# DRV8210PDSGR_2ways.net
KiCad netlist of a schematic drawn in EasyEDA Pro
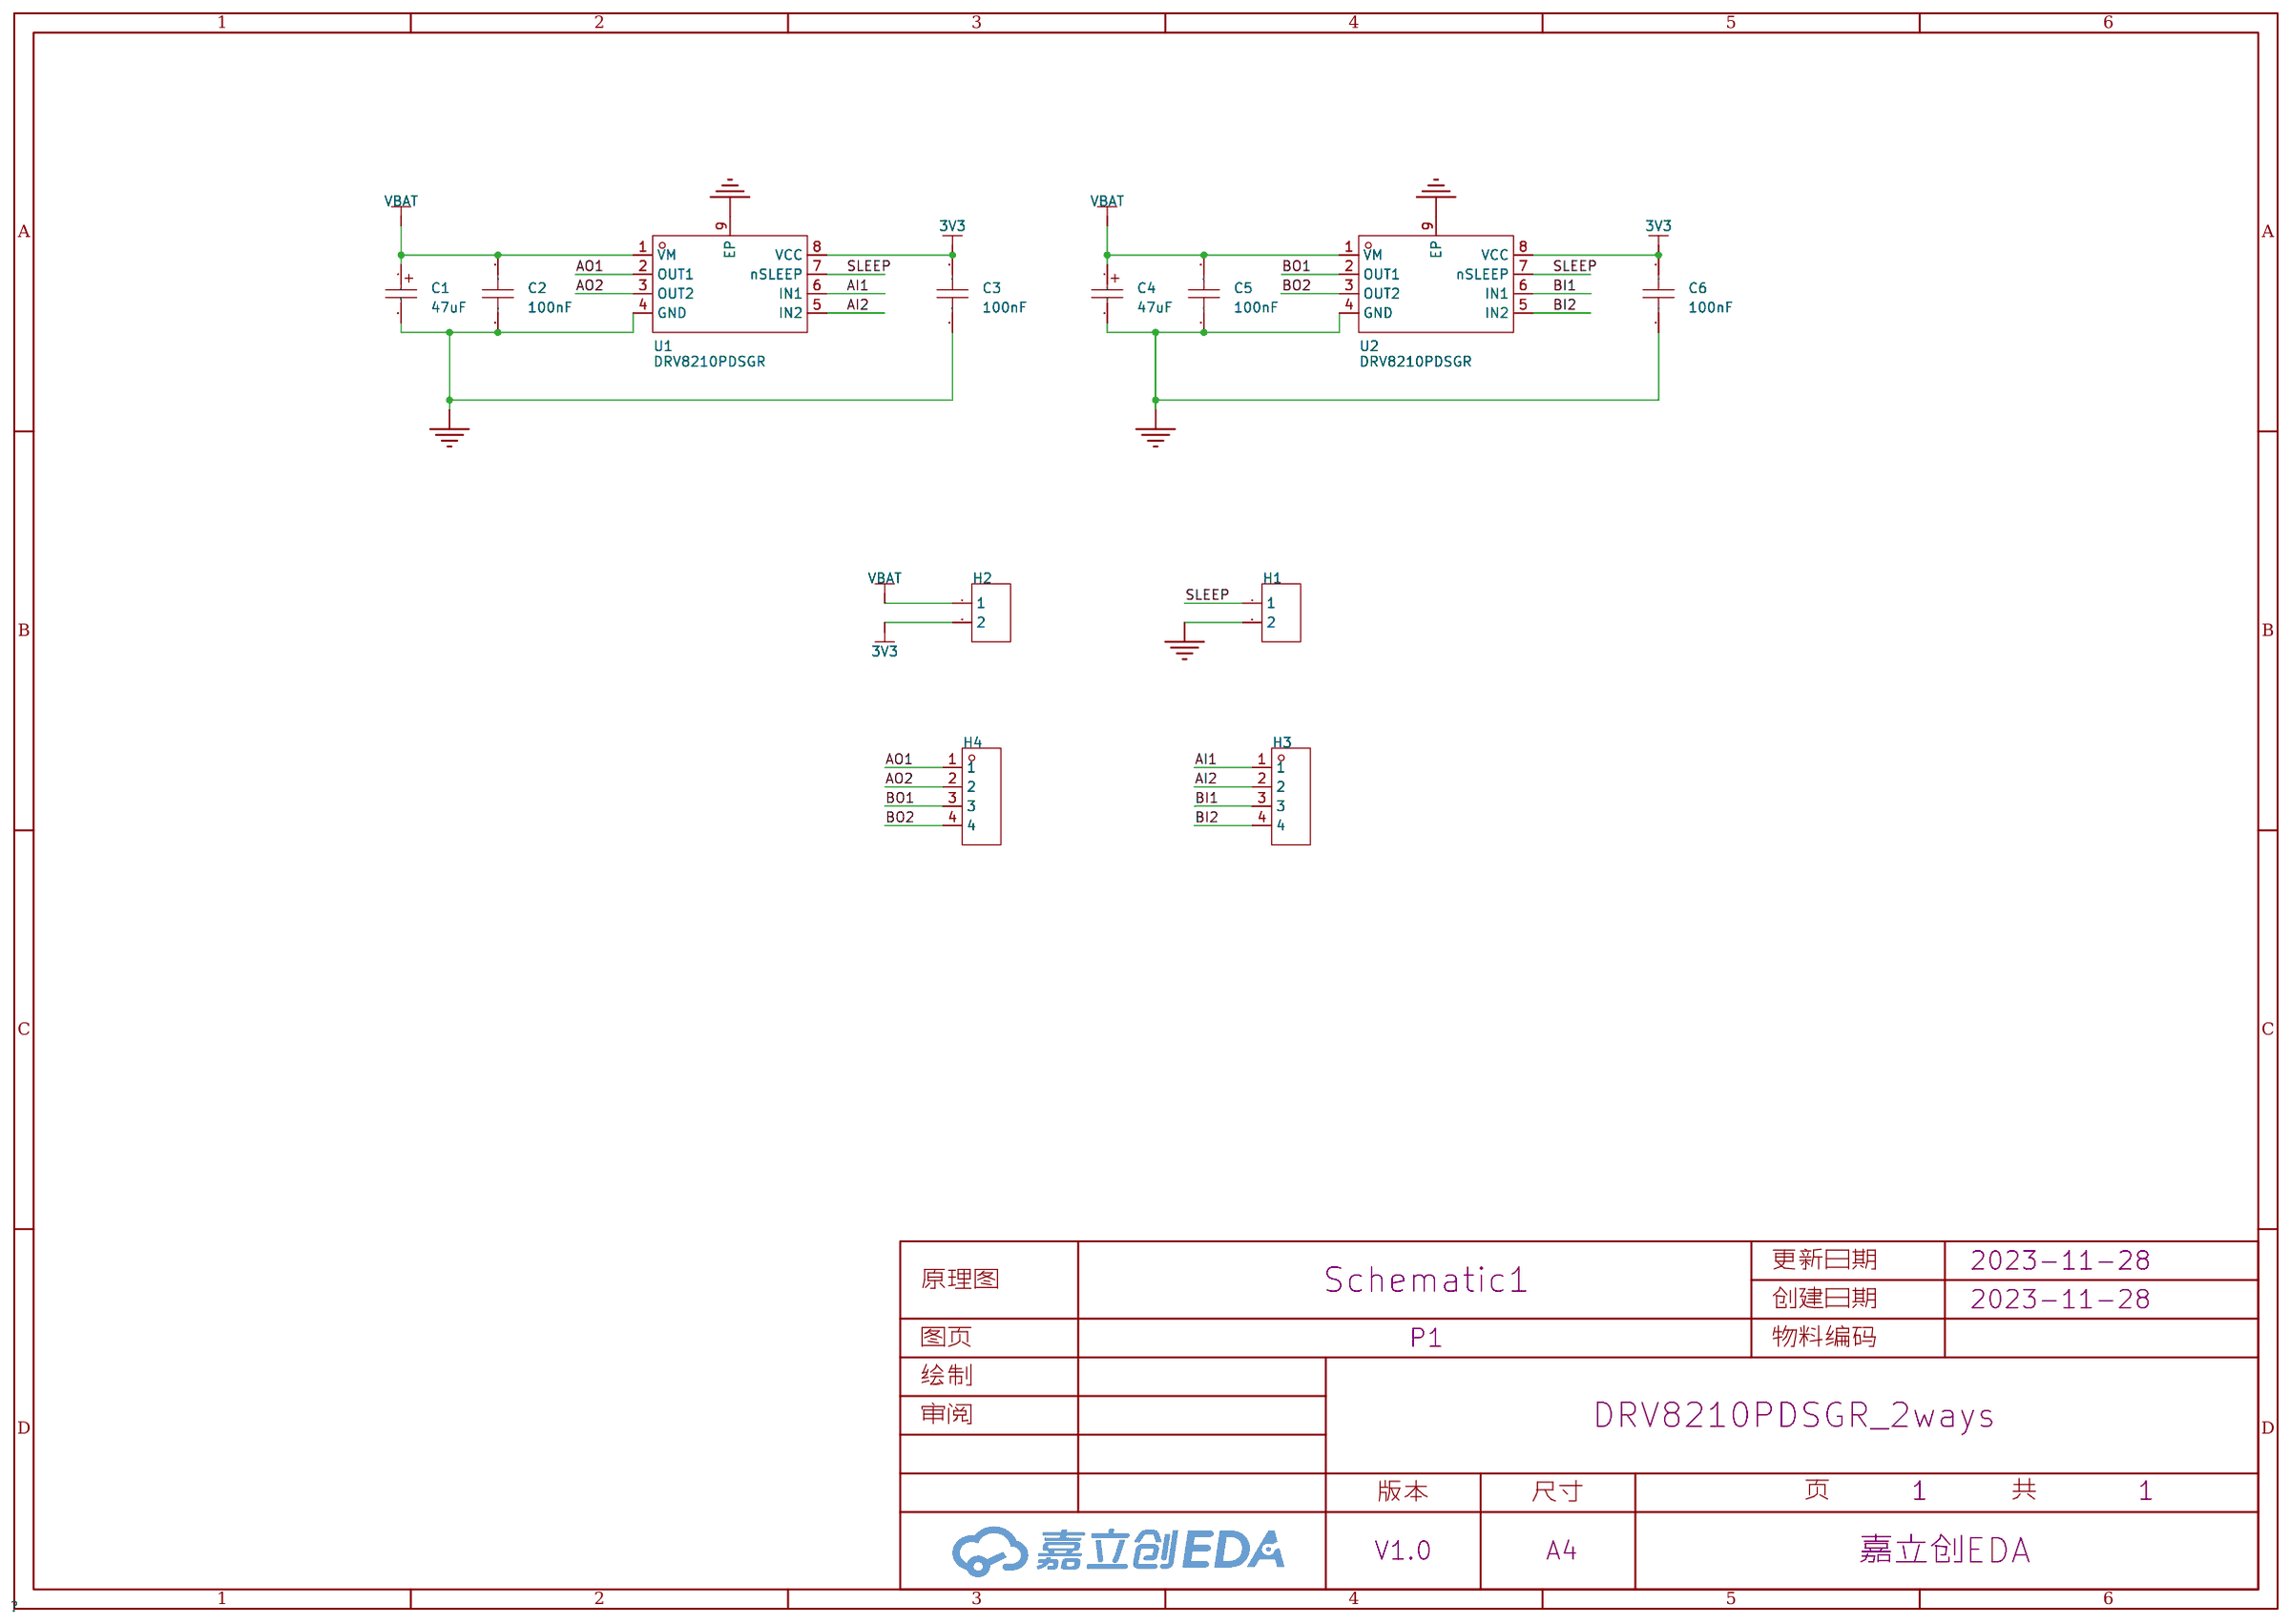
[diagram p0: schematic sheet]

(export (version "E")
  (design (tool "Eeschema 10.0.6"))
  (components
    (comp (ref "C1")
      (value "47uF")
      (footprint "easyedapro:CAP-SMD_L3.5-W2.8-R-RD")
      (description "容值:47uF;精度:±10%;额定电压:10V;等效串联电阻:1Ω@100kHz;")
      (fields (field (name "Manufacturer Part") "CA45-B010K476T") (field (name "Manufacturer") "湘怡中元/湘江"))
      (libsource (lib "easyedapro") (part "CA45-B010K476T"))
    )
    (comp (ref "C2")
      (value "100nF")
      (footprint "easyedapro:C0402")
      (libsource (lib "easyedapro") (part "CapAcitance"))
    )
    (comp (ref "C3")
      (value "100nF")
      (footprint "easyedapro:C0402")
      (libsource (lib "easyedapro") (part "CapAcitance"))
    )
    (comp (ref "C4")
      (value "47uF")
      (footprint "easyedapro:CAP-SMD_L3.5-W2.8-R-RD")
      (description "容值:47uF;精度:±10%;额定电压:10V;等效串联电阻:1Ω@100kHz;")
      (fields (field (name "Manufacturer Part") "CA45-B010K476T") (field (name "Manufacturer") "湘怡中元/湘江"))
      (libsource (lib "easyedapro") (part "CA45-B010K476T"))
    )
    (comp (ref "C5")
      (value "100nF")
      (footprint "easyedapro:C0402")
      (libsource (lib "easyedapro") (part "CapAcitance"))
    )
    (comp (ref "C6")
      (value "100nF")
      (footprint "easyedapro:C0402")
      (libsource (lib "easyedapro") (part "CapAcitance"))
    )
    (comp (ref "H1")
      (value "~")
      (footprint "easyedapro:HDR-TH_2P-P2.54-V-F")
      (libsource (lib "easyedapro") (part "Header-Female-2.54_1x2"))
    )
    (comp (ref "H2")
      (value "~")
      (footprint "easyedapro:HDR-TH_2P-P2.54-V-F")
      (libsource (lib "easyedapro") (part "Header-Female-2.54_1x2"))
    )
    (comp (ref "H3")
      (value "~")
      (footprint "easyedapro:HDR-TH_4P-P2.54-V-F")
      (libsource (lib "easyedapro") (part "2.54-1*4P母"))
    )
    (comp (ref "H4")
      (value "~")
      (footprint "easyedapro:HDR-TH_4P-P2.54-V-F")
      (libsource (lib "easyedapro") (part "2.54-1*4P母"))
    )
    (comp (ref "U1")
      (value "DRV8210PDSGR")
      (footprint "easyedapro:WSON-8_L2.0-W2.0-P0.50-TL-EP")
      (description "类型:有刷直流电机;电源电压:1.65V~12V;输出电流:1.76A;接口:PWM;")
      (fields (field (name "Manufacturer") "TI(德州仪器)"))
      (libsource (lib "easyedapro") (part "DRV8210PDSGR"))
    )
    (comp (ref "U2")
      (value "DRV8210PDSGR")
      (footprint "easyedapro:WSON-8_L2.0-W2.0-P0.50-TL-EP")
      (description "类型:有刷直流电机;电源电压:1.65V~12V;输出电流:1.76A;接口:PWM;")
      (fields (field (name "Manufacturer") "TI(德州仪器)"))
      (libsource (lib "easyedapro") (part "DRV8210PDSGR"))
    )
  )
  (nets
    (net (code "1") (name "/AI1") (class "Default")
      (node (ref "H3") (pin "1") (pinfunction "1_1") (pintype "unspecified"))
      (node (ref "U1") (pin "6") (pinfunction "IN1_6") (pintype "unspecified"))
    )
    (net (code "2") (name "/AI2") (class "Default")
      (node (ref "H3") (pin "2") (pinfunction "2_2") (pintype "unspecified"))
      (node (ref "U1") (pin "5") (pinfunction "IN2_5") (pintype "unspecified"))
    )
    (net (code "3") (name "/AO1") (class "Default")
      (node (ref "H4") (pin "1") (pinfunction "1_1") (pintype "unspecified"))
      (node (ref "U1") (pin "2") (pinfunction "OUT1_2") (pintype "unspecified"))
    )
    (net (code "4") (name "/AO2") (class "Default")
      (node (ref "H4") (pin "2") (pinfunction "2_2") (pintype "unspecified"))
      (node (ref "U1") (pin "3") (pinfunction "OUT2_3") (pintype "unspecified"))
    )
    (net (code "5") (name "/BI1") (class "Default")
      (node (ref "H3") (pin "3") (pinfunction "3_3") (pintype "unspecified"))
      (node (ref "U2") (pin "6") (pinfunction "IN1_6") (pintype "unspecified"))
    )
    (net (code "6") (name "/BI2") (class "Default")
      (node (ref "H3") (pin "4") (pinfunction "4_4") (pintype "unspecified"))
      (node (ref "U2") (pin "5") (pinfunction "IN2_5") (pintype "unspecified"))
    )
    (net (code "7") (name "/BO1") (class "Default")
      (node (ref "H4") (pin "3") (pinfunction "3_3") (pintype "unspecified"))
      (node (ref "U2") (pin "2") (pinfunction "OUT1_2") (pintype "unspecified"))
    )
    (net (code "8") (name "/BO2") (class "Default")
      (node (ref "H4") (pin "4") (pinfunction "4_4") (pintype "unspecified"))
      (node (ref "U2") (pin "3") (pinfunction "OUT2_3") (pintype "unspecified"))
    )
    (net (code "9") (name "/SLEEP") (class "Default")
      (node (ref "H1") (pin "1") (pinfunction "1_1") (pintype "input"))
      (node (ref "U1") (pin "7") (pinfunction "nSLEEP_7") (pintype "unspecified"))
      (node (ref "U2") (pin "7") (pinfunction "nSLEEP_7") (pintype "unspecified"))
    )
    (net (code "10") (name "3V3") (class "Default")
      (node (ref "C3") (pin "2") (pinfunction "2_2") (pintype "input"))
      (node (ref "C6") (pin "2") (pinfunction "2_2") (pintype "input"))
      (node (ref "H2") (pin "2") (pinfunction "2_2") (pintype "input"))
      (node (ref "U1") (pin "8") (pinfunction "VCC_8") (pintype "unspecified"))
      (node (ref "U2") (pin "8") (pinfunction "VCC_8") (pintype "unspecified"))
    )
    (net (code "11") (name "GND") (class "Default")
      (node (ref "C1") (pin "2") (pinfunction "2_2") (pintype "input"))
      (node (ref "C2") (pin "1") (pinfunction "1_1") (pintype "input"))
      (node (ref "C3") (pin "1") (pinfunction "1_1") (pintype "input"))
      (node (ref "C4") (pin "2") (pinfunction "2_2") (pintype "input"))
      (node (ref "C5") (pin "1") (pinfunction "1_1") (pintype "input"))
      (node (ref "C6") (pin "1") (pinfunction "1_1") (pintype "input"))
      (node (ref "H1") (pin "2") (pinfunction "2_2") (pintype "input"))
      (node (ref "U1") (pin "4") (pinfunction "GND_4") (pintype "unspecified"))
      (node (ref "U1") (pin "9") (pinfunction "EP_9") (pintype "unspecified"))
      (node (ref "U2") (pin "4") (pinfunction "GND_4") (pintype "unspecified"))
      (node (ref "U2") (pin "9") (pinfunction "EP_9") (pintype "unspecified"))
    )
    (net (code "12") (name "VBAT") (class "Default")
      (node (ref "C1") (pin "1") (pinfunction "1_1") (pintype "input"))
      (node (ref "C2") (pin "2") (pinfunction "2_2") (pintype "input"))
      (node (ref "C4") (pin "1") (pinfunction "1_1") (pintype "input"))
      (node (ref "C5") (pin "2") (pinfunction "2_2") (pintype "input"))
      (node (ref "H2") (pin "1") (pinfunction "1_1") (pintype "input"))
      (node (ref "U1") (pin "1") (pinfunction "VM_1") (pintype "unspecified"))
      (node (ref "U2") (pin "1") (pinfunction "VM_1") (pintype "unspecified"))
    )
  )
)
